# 7seg.net
KiCad netlist of a schematic drawn in EAGLE
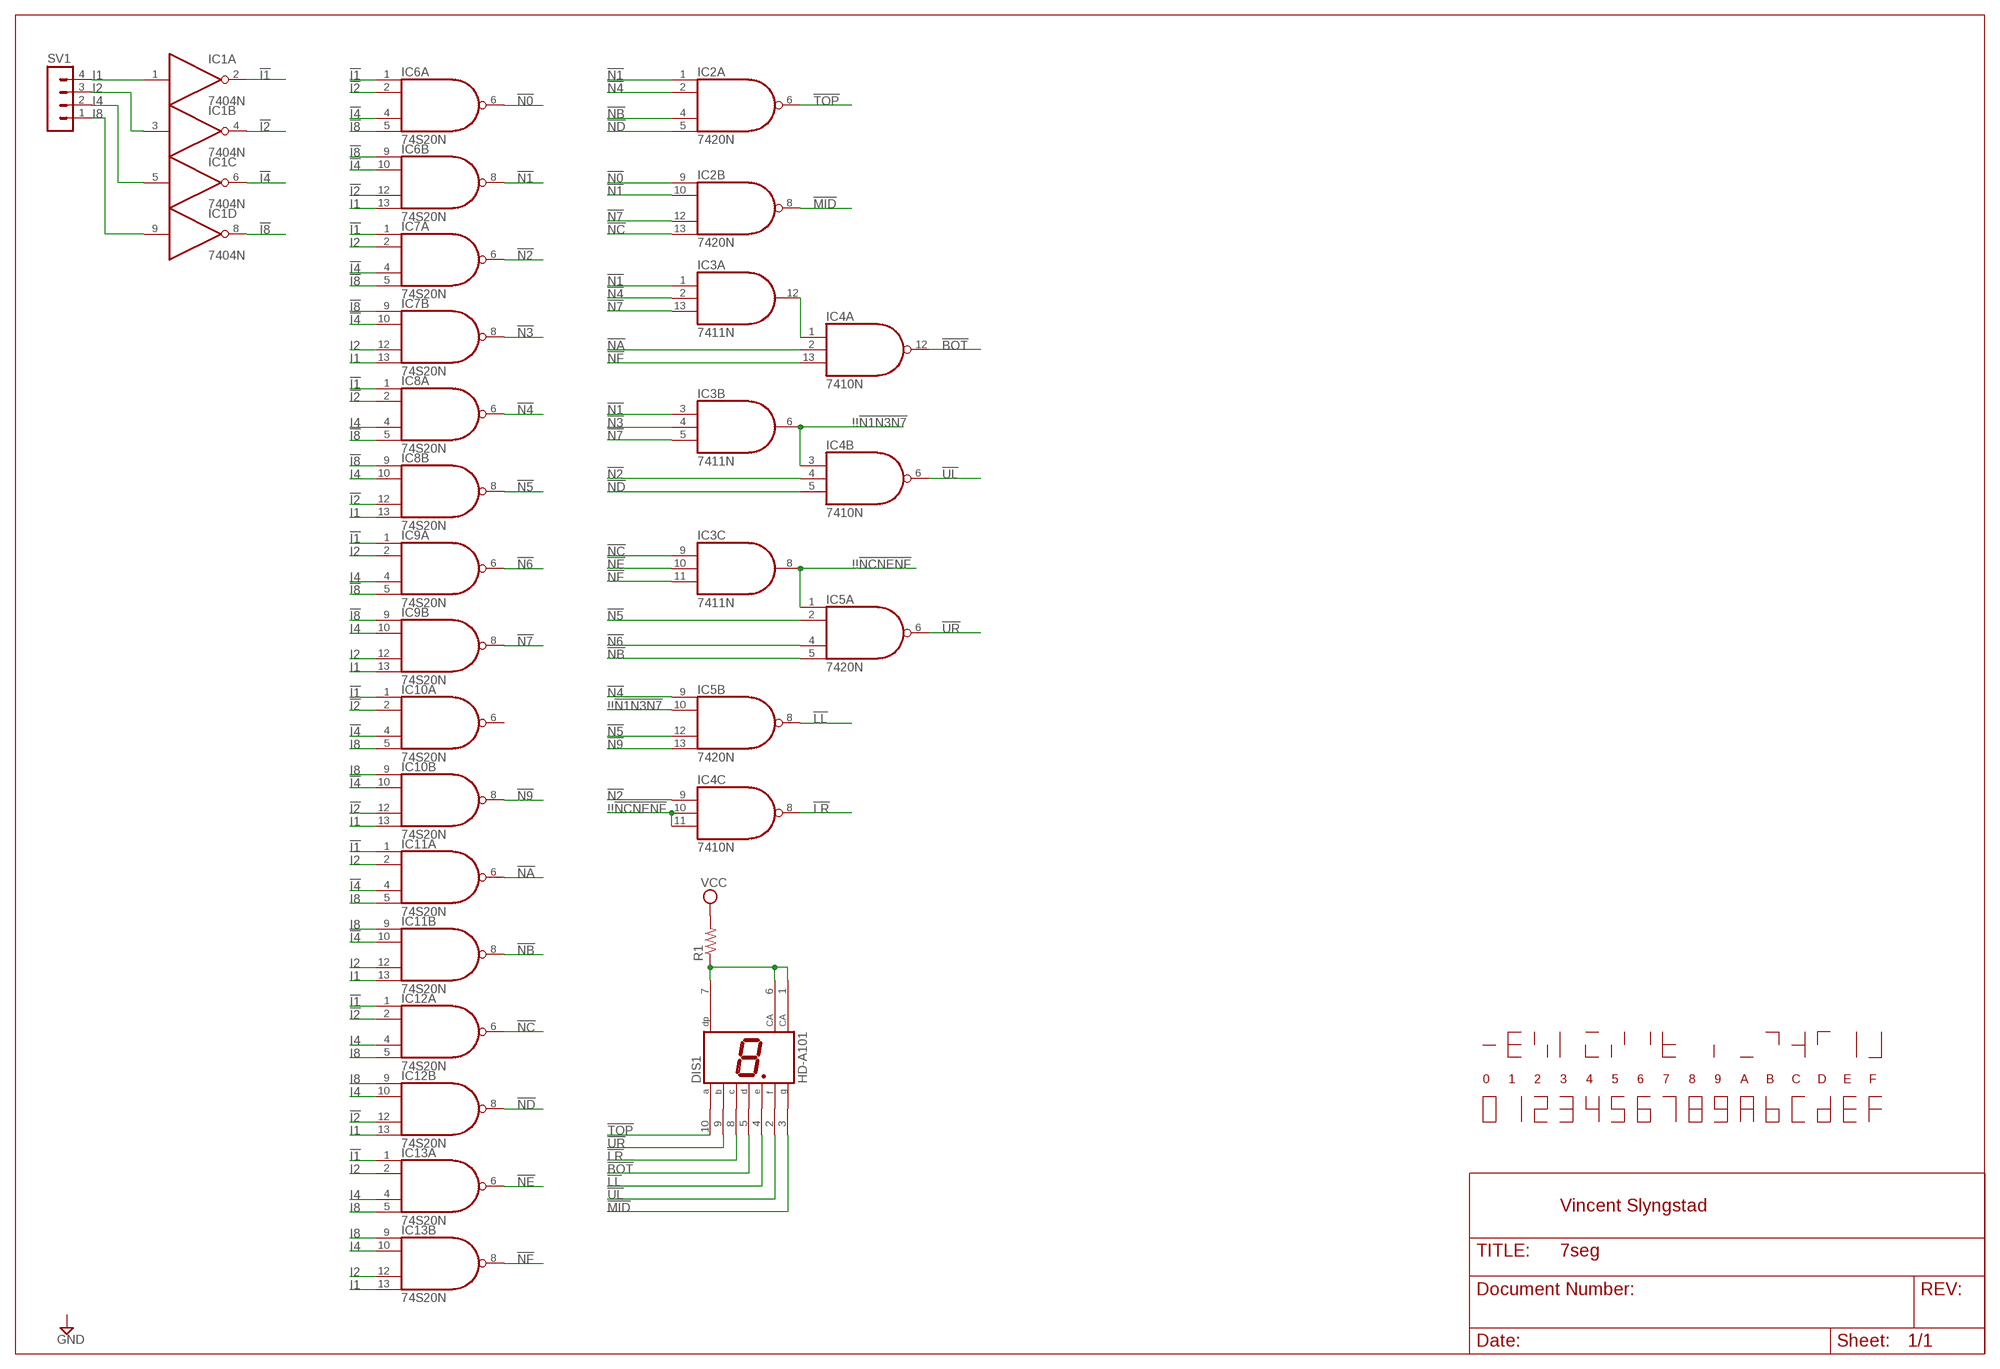
[diagram p0: schematic, sheet 1]

(export (version "E")
  (design (tool "Eeschema 10.0.6"))
  (components
    (comp (ref "DIS1")
      (value "HD-A101")
      (footprint "eagle-import:HDSP-A")
      (libsource (lib "eagle-import") (part "HD-A101"))
    )
    (comp (ref "IC1")
      (value "7404N")
      (footprint "eagle-import:DIL14")
      (libsource (lib "eagle-import") (part "7404N"))
    )
    (comp (ref "IC2")
      (value "7420N")
      (footprint "eagle-import:DIL14")
      (libsource (lib "eagle-import") (part "7420NS"))
    )
    (comp (ref "IC3")
      (value "7411N")
      (footprint "eagle-import:DIL14")
      (libsource (lib "eagle-import") (part "7411NS"))
    )
    (comp (ref "IC4")
      (value "7410N")
      (footprint "eagle-import:DIL14")
      (libsource (lib "eagle-import") (part "7410N"))
    )
    (comp (ref "IC5")
      (value "7420N")
      (footprint "eagle-import:DIL14")
      (libsource (lib "eagle-import") (part "7420NS"))
    )
    (comp (ref "IC6")
      (value "74S20N")
      (footprint "eagle-import:DIL14")
      (libsource (lib "eagle-import") (part "7420NS"))
    )
    (comp (ref "IC7")
      (value "74S20N")
      (footprint "eagle-import:DIL14")
      (libsource (lib "eagle-import") (part "7420NS"))
    )
    (comp (ref "IC8")
      (value "74S20N")
      (footprint "eagle-import:DIL14")
      (libsource (lib "eagle-import") (part "7420NS"))
    )
    (comp (ref "IC9")
      (value "74S20N")
      (footprint "eagle-import:DIL14")
      (libsource (lib "eagle-import") (part "7420NS"))
    )
    (comp (ref "IC10")
      (value "74S20N")
      (footprint "eagle-import:DIL14")
      (libsource (lib "eagle-import") (part "7420NS"))
    )
    (comp (ref "IC11")
      (value "74S20N")
      (footprint "eagle-import:DIL14")
      (libsource (lib "eagle-import") (part "7420NS"))
    )
    (comp (ref "IC12")
      (value "74S20N")
      (footprint "eagle-import:DIL14")
      (libsource (lib "eagle-import") (part "7420NS"))
    )
    (comp (ref "IC13")
      (value "74S20N")
      (footprint "eagle-import:DIL14")
      (libsource (lib "eagle-import") (part "7420NS"))
    )
    (comp (ref "R1")
      (value "R-US_0207/10")
      (footprint "eagle-import:0207_10")
      (libsource (lib "eagle-import") (part "R-US_0207/10"))
    )
    (comp (ref "SV1")
      (value "MA04-1")
      (footprint "eagle-import:MA04-1")
      (libsource (lib "eagle-import") (part "MA04-1"))
    )
  )
  (nets
    (net (code "1") (name "/I1") (class "Default")
      (node (ref "IC1") (pin "1") (pinfunction "I_1") (pintype "input"))
      (node (ref "IC10") (pin "13") (pinfunction "I3_13") (pintype "input"))
      (node (ref "IC11") (pin "13") (pinfunction "I3_13") (pintype "input"))
      (node (ref "IC12") (pin "13") (pinfunction "I3_13") (pintype "input"))
      (node (ref "IC13") (pin "13") (pinfunction "I3_13") (pintype "input"))
      (node (ref "IC6") (pin "13") (pinfunction "I3_13") (pintype "input"))
      (node (ref "IC7") (pin "13") (pinfunction "I3_13") (pintype "input"))
      (node (ref "IC8") (pin "13") (pinfunction "I3_13") (pintype "input"))
      (node (ref "IC9") (pin "13") (pinfunction "I3_13") (pintype "input"))
      (node (ref "SV1") (pin "4") (pinfunction "4_4") (pintype "passive"))
    )
    (net (code "2") (name "/I2") (class "Default")
      (node (ref "IC1") (pin "3") (pinfunction "I_3") (pintype "input"))
      (node (ref "IC11") (pin "12") (pinfunction "I2_12") (pintype "input"))
      (node (ref "IC11") (pin "2") (pinfunction "I1_2") (pintype "input"))
      (node (ref "IC13") (pin "12") (pinfunction "I2_12") (pintype "input"))
      (node (ref "IC13") (pin "2") (pinfunction "I1_2") (pintype "input"))
      (node (ref "IC7") (pin "12") (pinfunction "I2_12") (pintype "input"))
      (node (ref "IC7") (pin "2") (pinfunction "I1_2") (pintype "input"))
      (node (ref "IC9") (pin "12") (pinfunction "I2_12") (pintype "input"))
      (node (ref "IC9") (pin "2") (pinfunction "I1_2") (pintype "input"))
      (node (ref "SV1") (pin "3") (pinfunction "3_3") (pintype "passive"))
    )
    (net (code "3") (name "/I4") (class "Default")
      (node (ref "IC1") (pin "5") (pinfunction "I_5") (pintype "input"))
      (node (ref "IC12") (pin "10") (pinfunction "I1_10") (pintype "input"))
      (node (ref "IC12") (pin "4") (pinfunction "I2_4") (pintype "input"))
      (node (ref "IC13") (pin "10") (pinfunction "I1_10") (pintype "input"))
      (node (ref "IC13") (pin "4") (pinfunction "I2_4") (pintype "input"))
      (node (ref "IC8") (pin "10") (pinfunction "I1_10") (pintype "input"))
      (node (ref "IC8") (pin "4") (pinfunction "I2_4") (pintype "input"))
      (node (ref "IC9") (pin "10") (pinfunction "I1_10") (pintype "input"))
      (node (ref "IC9") (pin "4") (pinfunction "I2_4") (pintype "input"))
      (node (ref "SV1") (pin "2") (pinfunction "2_2") (pintype "passive"))
    )
    (net (code "4") (name "/I8") (class "Default")
      (node (ref "IC1") (pin "9") (pinfunction "I_9") (pintype "input"))
      (node (ref "IC10") (pin "5") (pinfunction "I3_5") (pintype "input"))
      (node (ref "IC10") (pin "9") (pinfunction "I0_9") (pintype "input"))
      (node (ref "IC11") (pin "5") (pinfunction "I3_5") (pintype "input"))
      (node (ref "IC11") (pin "9") (pinfunction "I0_9") (pintype "input"))
      (node (ref "IC12") (pin "5") (pinfunction "I3_5") (pintype "input"))
      (node (ref "IC12") (pin "9") (pinfunction "I0_9") (pintype "input"))
      (node (ref "IC13") (pin "5") (pinfunction "I3_5") (pintype "input"))
      (node (ref "IC13") (pin "9") (pinfunction "I0_9") (pintype "input"))
      (node (ref "SV1") (pin "1") (pinfunction "1_1") (pintype "passive"))
    )
    (net (code "5") (name "/~{BOT}") (class "Default")
      (node (ref "DIS1") (pin "5") (pinfunction "D_5") (pintype "passive"))
      (node (ref "IC4") (pin "12") (pinfunction "O_12") (pintype "output"))
    )
    (net (code "6") (name "/~{I1}") (class "Default")
      (node (ref "IC1") (pin "2") (pinfunction "O_2") (pintype "output"))
      (node (ref "IC10") (pin "1") (pinfunction "I0_1") (pintype "input"))
      (node (ref "IC11") (pin "1") (pinfunction "I0_1") (pintype "input"))
      (node (ref "IC12") (pin "1") (pinfunction "I0_1") (pintype "input"))
      (node (ref "IC13") (pin "1") (pinfunction "I0_1") (pintype "input"))
      (node (ref "IC6") (pin "1") (pinfunction "I0_1") (pintype "input"))
      (node (ref "IC7") (pin "1") (pinfunction "I0_1") (pintype "input"))
      (node (ref "IC8") (pin "1") (pinfunction "I0_1") (pintype "input"))
      (node (ref "IC9") (pin "1") (pinfunction "I0_1") (pintype "input"))
    )
    (net (code "7") (name "/~{I2}") (class "Default")
      (node (ref "IC1") (pin "4") (pinfunction "O_4") (pintype "output"))
      (node (ref "IC10") (pin "12") (pinfunction "I2_12") (pintype "input"))
      (node (ref "IC10") (pin "2") (pinfunction "I1_2") (pintype "input"))
      (node (ref "IC12") (pin "12") (pinfunction "I2_12") (pintype "input"))
      (node (ref "IC12") (pin "2") (pinfunction "I1_2") (pintype "input"))
      (node (ref "IC6") (pin "12") (pinfunction "I2_12") (pintype "input"))
      (node (ref "IC6") (pin "2") (pinfunction "I1_2") (pintype "input"))
      (node (ref "IC8") (pin "12") (pinfunction "I2_12") (pintype "input"))
      (node (ref "IC8") (pin "2") (pinfunction "I1_2") (pintype "input"))
    )
    (net (code "8") (name "/~{I4}") (class "Default")
      (node (ref "IC1") (pin "6") (pinfunction "O_6") (pintype "output"))
      (node (ref "IC10") (pin "10") (pinfunction "I1_10") (pintype "input"))
      (node (ref "IC10") (pin "4") (pinfunction "I2_4") (pintype "input"))
      (node (ref "IC11") (pin "10") (pinfunction "I1_10") (pintype "input"))
      (node (ref "IC11") (pin "4") (pinfunction "I2_4") (pintype "input"))
      (node (ref "IC6") (pin "10") (pinfunction "I1_10") (pintype "input"))
      (node (ref "IC6") (pin "4") (pinfunction "I2_4") (pintype "input"))
      (node (ref "IC7") (pin "10") (pinfunction "I1_10") (pintype "input"))
      (node (ref "IC7") (pin "4") (pinfunction "I2_4") (pintype "input"))
    )
    (net (code "9") (name "/~{I8}") (class "Default")
      (node (ref "IC1") (pin "8") (pinfunction "O_8") (pintype "output"))
      (node (ref "IC6") (pin "5") (pinfunction "I3_5") (pintype "input"))
      (node (ref "IC6") (pin "9") (pinfunction "I0_9") (pintype "input"))
      (node (ref "IC7") (pin "5") (pinfunction "I3_5") (pintype "input"))
      (node (ref "IC7") (pin "9") (pinfunction "I0_9") (pintype "input"))
      (node (ref "IC8") (pin "5") (pinfunction "I3_5") (pintype "input"))
      (node (ref "IC8") (pin "9") (pinfunction "I0_9") (pintype "input"))
      (node (ref "IC9") (pin "5") (pinfunction "I3_5") (pintype "input"))
      (node (ref "IC9") (pin "9") (pinfunction "I0_9") (pintype "input"))
    )
    (net (code "10") (name "/~{LL}") (class "Default")
      (node (ref "DIS1") (pin "4") (pinfunction "E_4") (pintype "passive"))
      (node (ref "IC5") (pin "8") (pinfunction "O_8") (pintype "output"))
    )
    (net (code "11") (name "/~{LR}") (class "Default")
      (node (ref "DIS1") (pin "8") (pinfunction "C_8") (pintype "passive"))
      (node (ref "IC4") (pin "8") (pinfunction "O_8") (pintype "output"))
    )
    (net (code "12") (name "/~{MID}") (class "Default")
      (node (ref "DIS1") (pin "3") (pinfunction "G_3") (pintype "passive"))
      (node (ref "IC2") (pin "8") (pinfunction "O_8") (pintype "output"))
    )
    (net (code "13") (name "/~{N0}") (class "Default")
      (node (ref "IC2") (pin "9") (pinfunction "I0_9") (pintype "input"))
      (node (ref "IC6") (pin "6") (pinfunction "O_6") (pintype "output"))
    )
    (net (code "14") (name "/~{N1}") (class "Default")
      (node (ref "IC2") (pin "1") (pinfunction "I0_1") (pintype "input"))
      (node (ref "IC2") (pin "10") (pinfunction "I1_10") (pintype "input"))
      (node (ref "IC3") (pin "1") (pinfunction "I0_1") (pintype "input"))
      (node (ref "IC3") (pin "3") (pinfunction "I0_3") (pintype "input"))
      (node (ref "IC6") (pin "8") (pinfunction "O_8") (pintype "output"))
    )
    (net (code "15") (name "/~{N2}") (class "Default")
      (node (ref "IC4") (pin "4") (pinfunction "I1_4") (pintype "input"))
      (node (ref "IC4") (pin "9") (pinfunction "I0_9") (pintype "input"))
      (node (ref "IC7") (pin "6") (pinfunction "O_6") (pintype "output"))
    )
    (net (code "16") (name "/~{N3}") (class "Default")
      (node (ref "IC3") (pin "4") (pinfunction "I1_4") (pintype "input"))
      (node (ref "IC7") (pin "8") (pinfunction "O_8") (pintype "output"))
    )
    (net (code "17") (name "/~{N4}") (class "Default")
      (node (ref "IC2") (pin "2") (pinfunction "I1_2") (pintype "input"))
      (node (ref "IC3") (pin "2") (pinfunction "I1_2") (pintype "input"))
      (node (ref "IC5") (pin "9") (pinfunction "I0_9") (pintype "input"))
      (node (ref "IC8") (pin "6") (pinfunction "O_6") (pintype "output"))
    )
    (net (code "18") (name "/~{N5}") (class "Default")
      (node (ref "IC5") (pin "12") (pinfunction "I2_12") (pintype "input"))
      (node (ref "IC5") (pin "2") (pinfunction "I1_2") (pintype "input"))
      (node (ref "IC8") (pin "8") (pinfunction "O_8") (pintype "output"))
    )
    (net (code "19") (name "/~{N6}") (class "Default")
      (node (ref "IC5") (pin "4") (pinfunction "I2_4") (pintype "input"))
      (node (ref "IC9") (pin "6") (pinfunction "O_6") (pintype "output"))
    )
    (net (code "20") (name "/~{N7}") (class "Default")
      (node (ref "IC2") (pin "12") (pinfunction "I2_12") (pintype "input"))
      (node (ref "IC3") (pin "13") (pinfunction "I2_13") (pintype "input"))
      (node (ref "IC3") (pin "5") (pinfunction "I2_5") (pintype "input"))
      (node (ref "IC9") (pin "8") (pinfunction "O_8") (pintype "output"))
    )
    (net (code "21") (name "/~{N9}") (class "Default")
      (node (ref "IC10") (pin "8") (pinfunction "O_8") (pintype "output"))
      (node (ref "IC5") (pin "13") (pinfunction "I3_13") (pintype "input"))
    )
    (net (code "22") (name "/~{NA}") (class "Default")
      (node (ref "IC11") (pin "6") (pinfunction "O_6") (pintype "output"))
      (node (ref "IC4") (pin "2") (pinfunction "I1_2") (pintype "input"))
    )
    (net (code "23") (name "/~{NB}") (class "Default")
      (node (ref "IC11") (pin "8") (pinfunction "O_8") (pintype "output"))
      (node (ref "IC2") (pin "4") (pinfunction "I2_4") (pintype "input"))
      (node (ref "IC5") (pin "5") (pinfunction "I3_5") (pintype "input"))
    )
    (net (code "24") (name "/~{NC}") (class "Default")
      (node (ref "IC12") (pin "6") (pinfunction "O_6") (pintype "output"))
      (node (ref "IC2") (pin "13") (pinfunction "I3_13") (pintype "input"))
      (node (ref "IC3") (pin "9") (pinfunction "I0_9") (pintype "input"))
    )
    (net (code "25") (name "/~{ND}") (class "Default")
      (node (ref "IC12") (pin "8") (pinfunction "O_8") (pintype "output"))
      (node (ref "IC2") (pin "5") (pinfunction "I3_5") (pintype "input"))
      (node (ref "IC4") (pin "5") (pinfunction "I2_5") (pintype "input"))
    )
    (net (code "26") (name "/~{NE}") (class "Default")
      (node (ref "IC13") (pin "6") (pinfunction "O_6") (pintype "output"))
      (node (ref "IC3") (pin "10") (pinfunction "I1_10") (pintype "input"))
    )
    (net (code "27") (name "/~{NF}") (class "Default")
      (node (ref "IC13") (pin "8") (pinfunction "O_8") (pintype "output"))
      (node (ref "IC3") (pin "11") (pinfunction "I2_11") (pintype "input"))
      (node (ref "IC4") (pin "13") (pinfunction "I2_13") (pintype "input"))
    )
    (net (code "28") (name "/~{TOP}") (class "Default")
      (node (ref "DIS1") (pin "10") (pinfunction "A_10") (pintype "passive"))
      (node (ref "IC2") (pin "6") (pinfunction "O_6") (pintype "output"))
    )
    (net (code "29") (name "/~{UL}") (class "Default")
      (node (ref "DIS1") (pin "2") (pinfunction "F_2") (pintype "passive"))
      (node (ref "IC4") (pin "6") (pinfunction "O_6") (pintype "output"))
    )
    (net (code "30") (name "/~{UR}") (class "Default")
      (node (ref "DIS1") (pin "9") (pinfunction "B_9") (pintype "passive"))
      (node (ref "IC5") (pin "6") (pinfunction "O_6") (pintype "output"))
    )
    (net (code "31") (name "/~~{N1N3N7}") (class "Default")
      (node (ref "IC3") (pin "6") (pinfunction "O_6") (pintype "output"))
      (node (ref "IC4") (pin "3") (pinfunction "I0_3") (pintype "input"))
      (node (ref "IC5") (pin "10") (pinfunction "I1_10") (pintype "input"))
    )
    (net (code "32") (name "/~~{NCNENF}") (class "Default")
      (node (ref "IC3") (pin "8") (pinfunction "O_8") (pintype "output"))
      (node (ref "IC4") (pin "10") (pinfunction "I1_10") (pintype "input"))
      (node (ref "IC4") (pin "11") (pinfunction "I2_11") (pintype "input"))
      (node (ref "IC5") (pin "1") (pinfunction "I0_1") (pintype "input"))
    )
    (net (code "34") (name "Net-(DIS1-DP)") (class "Default")
      (node (ref "DIS1") (pin "1") (pinfunction "CA_1") (pintype "passive"))
      (node (ref "DIS1") (pin "6") (pinfunction "CA_6") (pintype "passive"))
      (node (ref "DIS1") (pin "7") (pinfunction "DP_7") (pintype "passive"))
      (node (ref "R1") (pin "1") (pinfunction "1_1") (pintype "passive"))
    )
    (net (code "35") (name "Net-(IC3A-O)") (class "Default")
      (node (ref "IC3") (pin "12") (pinfunction "O_12") (pintype "output"))
      (node (ref "IC4") (pin "1") (pinfunction "I0_1") (pintype "input"))
    )
    (net (code "36") (name "VCC") (class "Default")
      (node (ref "R1") (pin "2") (pinfunction "2_2") (pintype "passive"))
    )
    (net (code "37") (name "unconnected-(IC10A-O-Pad6)") (class "Default")
      (node (ref "IC10") (pin "6") (pinfunction "O_6") (pintype "output"))
    )
  )
)
